# ai_orb-16.net
KiCad netlist of a schematic drawn in EAGLE
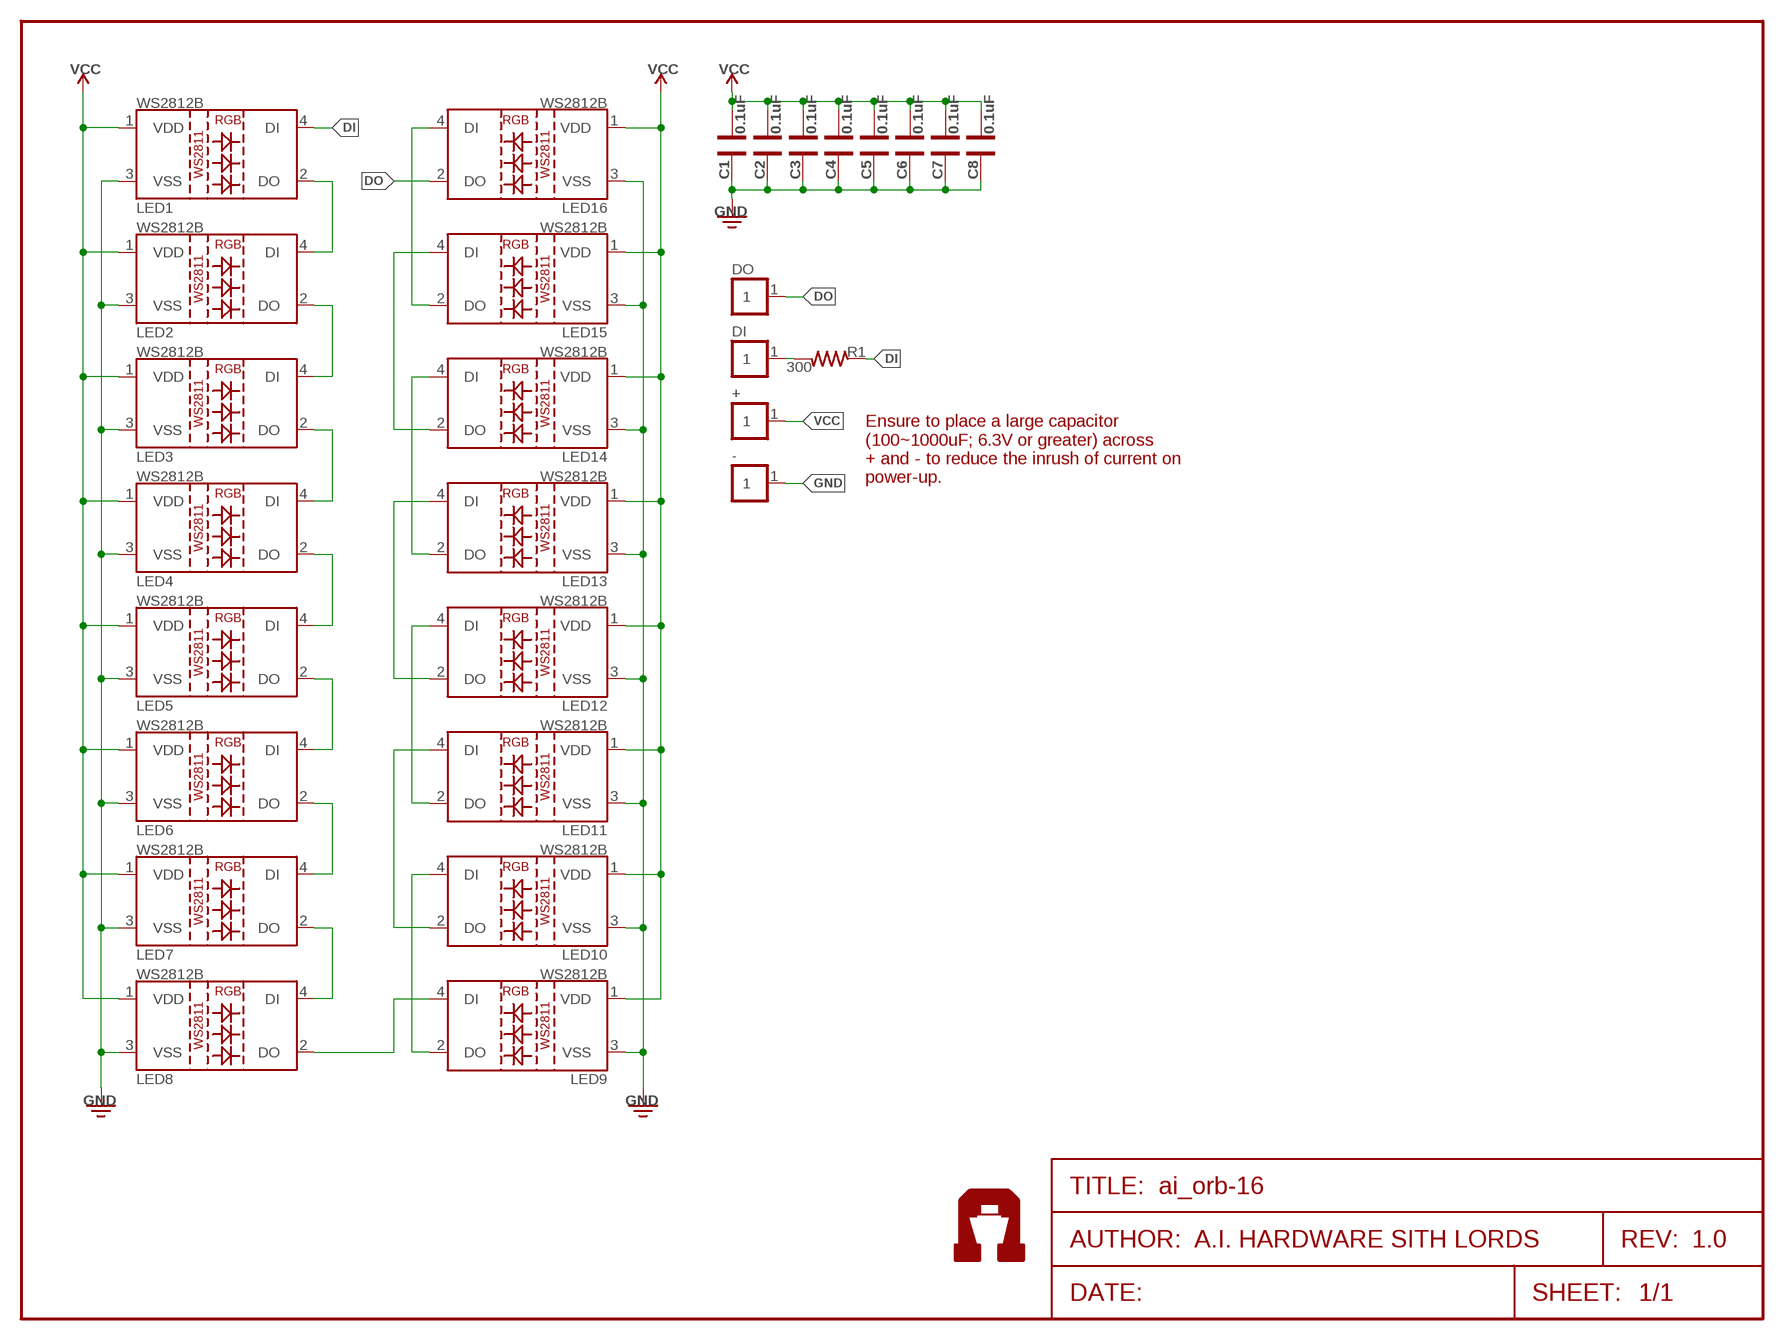
[diagram p0: schematic, sheet 1]

(export (version "E")
  (design (tool "Eeschema 10.0.6"))
  (components
    (comp (ref "+")
      (value "1X01-SM")
      (footprint "eagle-import:1X01-SM")
      (libsource (lib "eagle-import") (part "1X01-SM"))
    )
    (comp (ref "-")
      (value "1X01-SM")
      (footprint "eagle-import:1X01-SM")
      (libsource (lib "eagle-import") (part "1X01-SM"))
    )
    (comp (ref "C1")
      (value "0.1uF")
      (footprint "eagle-import:CAP-0402")
      (libsource (lib "eagle-import") (part "CAP0402"))
    )
    (comp (ref "C2")
      (value "0.1uF")
      (footprint "eagle-import:CAP-0402")
      (libsource (lib "eagle-import") (part "CAP0402"))
    )
    (comp (ref "C3")
      (value "0.1uF")
      (footprint "eagle-import:CAP-0402")
      (libsource (lib "eagle-import") (part "CAP0402"))
    )
    (comp (ref "C4")
      (value "0.1uF")
      (footprint "eagle-import:CAP-0402")
      (libsource (lib "eagle-import") (part "CAP0402"))
    )
    (comp (ref "C5")
      (value "0.1uF")
      (footprint "eagle-import:CAP-0402")
      (libsource (lib "eagle-import") (part "CAP0402"))
    )
    (comp (ref "C6")
      (value "0.1uF")
      (footprint "eagle-import:CAP-0402")
      (libsource (lib "eagle-import") (part "CAP0402"))
    )
    (comp (ref "C7")
      (value "0.1uF")
      (footprint "eagle-import:CAP-0402")
      (libsource (lib "eagle-import") (part "CAP0402"))
    )
    (comp (ref "C8")
      (value "0.1uF")
      (footprint "eagle-import:CAP-0402")
      (libsource (lib "eagle-import") (part "CAP0402"))
    )
    (comp (ref "DI")
      (value "1X01-SM")
      (footprint "eagle-import:1X01-SM")
      (libsource (lib "eagle-import") (part "1X01-SM"))
    )
    (comp (ref "DO")
      (value "1X01-SM")
      (footprint "eagle-import:1X01-SM")
      (libsource (lib "eagle-import") (part "1X01-SM"))
    )
    (comp (ref "LED1")
      (value "LED-WS2812B-SM")
      (footprint "eagle-import:LED-WS2812B-SM")
      (libsource (lib "eagle-import") (part "LED-WS2812B-SM"))
    )
    (comp (ref "LED2")
      (value "LED-WS2812B-SM")
      (footprint "eagle-import:LED-WS2812B-SM")
      (libsource (lib "eagle-import") (part "LED-WS2812B-SM"))
    )
    (comp (ref "LED3")
      (value "LED-WS2812B-SM")
      (footprint "eagle-import:LED-WS2812B-SM")
      (libsource (lib "eagle-import") (part "LED-WS2812B-SM"))
    )
    (comp (ref "LED4")
      (value "LED-WS2812B-SM")
      (footprint "eagle-import:LED-WS2812B-SM")
      (libsource (lib "eagle-import") (part "LED-WS2812B-SM"))
    )
    (comp (ref "LED5")
      (value "LED-WS2812B-SM")
      (footprint "eagle-import:LED-WS2812B-SM")
      (libsource (lib "eagle-import") (part "LED-WS2812B-SM"))
    )
    (comp (ref "LED6")
      (value "LED-WS2812B-SM")
      (footprint "eagle-import:LED-WS2812B-SM")
      (libsource (lib "eagle-import") (part "LED-WS2812B-SM"))
    )
    (comp (ref "LED7")
      (value "LED-WS2812B-SM")
      (footprint "eagle-import:LED-WS2812B-SM")
      (libsource (lib "eagle-import") (part "LED-WS2812B-SM"))
    )
    (comp (ref "LED8")
      (value "LED-WS2812B-SM")
      (footprint "eagle-import:LED-WS2812B-SM")
      (libsource (lib "eagle-import") (part "LED-WS2812B-SM"))
    )
    (comp (ref "LED9")
      (value "LED-WS2812B-SM")
      (footprint "eagle-import:LED-WS2812B-SM")
      (libsource (lib "eagle-import") (part "LED-WS2812B-SM"))
    )
    (comp (ref "LED10")
      (value "LED-WS2812B-SM")
      (footprint "eagle-import:LED-WS2812B-SM")
      (libsource (lib "eagle-import") (part "LED-WS2812B-SM"))
    )
    (comp (ref "LED11")
      (value "LED-WS2812B-SM")
      (footprint "eagle-import:LED-WS2812B-SM")
      (libsource (lib "eagle-import") (part "LED-WS2812B-SM"))
    )
    (comp (ref "LED12")
      (value "LED-WS2812B-SM")
      (footprint "eagle-import:LED-WS2812B-SM")
      (libsource (lib "eagle-import") (part "LED-WS2812B-SM"))
    )
    (comp (ref "LED13")
      (value "LED-WS2812B-SM")
      (footprint "eagle-import:LED-WS2812B-SM")
      (libsource (lib "eagle-import") (part "LED-WS2812B-SM"))
    )
    (comp (ref "LED14")
      (value "LED-WS2812B-SM")
      (footprint "eagle-import:LED-WS2812B-SM")
      (libsource (lib "eagle-import") (part "LED-WS2812B-SM"))
    )
    (comp (ref "LED15")
      (value "LED-WS2812B-SM")
      (footprint "eagle-import:LED-WS2812B-SM")
      (libsource (lib "eagle-import") (part "LED-WS2812B-SM"))
    )
    (comp (ref "LED16")
      (value "LED-WS2812B-SM")
      (footprint "eagle-import:LED-WS2812B-SM")
      (libsource (lib "eagle-import") (part "LED-WS2812B-SM"))
    )
    (comp (ref "LOGO")
      (value "AI-LOGOXS")
      (footprint "eagle-import:AI-LOGO-XS")
      (libsource (lib "eagle-import") (part "AI-LOGOXS"))
    )
    (comp (ref "R1")
      (value "300")
      (footprint "eagle-import:RES-0402")
      (libsource (lib "eagle-import") (part "RES0402"))
    )
  )
  (nets
    (net (code "1") (name "DI") (class "Default")
      (node (ref "LED1") (pin "4") (pinfunction "DI_4") (pintype "bidirectional"))
      (node (ref "R1") (pin "1") (pinfunction "1_1") (pintype "passive"))
    )
    (net (code "2") (name "DO") (class "Default")
      (node (ref "DO") (pin "1") (pinfunction "1_1") (pintype "bidirectional"))
      (node (ref "LED16") (pin "2") (pinfunction "DO_2") (pintype "bidirectional"))
    )
    (net (code "3") (name "GND") (class "Default")
      (node (ref "-") (pin "1") (pinfunction "1_1") (pintype "bidirectional"))
      (node (ref "C1") (pin "2") (pinfunction "2_2") (pintype "passive"))
      (node (ref "C2") (pin "2") (pinfunction "2_2") (pintype "passive"))
      (node (ref "C3") (pin "2") (pinfunction "2_2") (pintype "passive"))
      (node (ref "C4") (pin "2") (pinfunction "2_2") (pintype "passive"))
      (node (ref "C5") (pin "2") (pinfunction "2_2") (pintype "passive"))
      (node (ref "C6") (pin "2") (pinfunction "2_2") (pintype "passive"))
      (node (ref "C7") (pin "2") (pinfunction "2_2") (pintype "passive"))
      (node (ref "C8") (pin "2") (pinfunction "2_2") (pintype "passive"))
      (node (ref "LED1") (pin "3") (pinfunction "VSS_3") (pintype "bidirectional"))
      (node (ref "LED10") (pin "3") (pinfunction "VSS_3") (pintype "bidirectional"))
      (node (ref "LED11") (pin "3") (pinfunction "VSS_3") (pintype "bidirectional"))
      (node (ref "LED12") (pin "3") (pinfunction "VSS_3") (pintype "bidirectional"))
      (node (ref "LED13") (pin "3") (pinfunction "VSS_3") (pintype "bidirectional"))
      (node (ref "LED14") (pin "3") (pinfunction "VSS_3") (pintype "bidirectional"))
      (node (ref "LED15") (pin "3") (pinfunction "VSS_3") (pintype "bidirectional"))
      (node (ref "LED16") (pin "3") (pinfunction "VSS_3") (pintype "bidirectional"))
      (node (ref "LED2") (pin "3") (pinfunction "VSS_3") (pintype "bidirectional"))
      (node (ref "LED3") (pin "3") (pinfunction "VSS_3") (pintype "bidirectional"))
      (node (ref "LED4") (pin "3") (pinfunction "VSS_3") (pintype "bidirectional"))
      (node (ref "LED5") (pin "3") (pinfunction "VSS_3") (pintype "bidirectional"))
      (node (ref "LED6") (pin "3") (pinfunction "VSS_3") (pintype "bidirectional"))
      (node (ref "LED7") (pin "3") (pinfunction "VSS_3") (pintype "bidirectional"))
      (node (ref "LED8") (pin "3") (pinfunction "VSS_3") (pintype "bidirectional"))
      (node (ref "LED9") (pin "3") (pinfunction "VSS_3") (pintype "bidirectional"))
    )
    (net (code "4") (name "Net-(DI-Pad1)") (class "Default")
      (node (ref "DI") (pin "1") (pinfunction "1_1") (pintype "bidirectional"))
      (node (ref "R1") (pin "2") (pinfunction "2_2") (pintype "passive"))
    )
    (net (code "5") (name "Net-(LED1-DO)") (class "Default")
      (node (ref "LED1") (pin "2") (pinfunction "DO_2") (pintype "bidirectional"))
      (node (ref "LED2") (pin "4") (pinfunction "DI_4") (pintype "bidirectional"))
    )
    (net (code "6") (name "Net-(LED2-DO)") (class "Default")
      (node (ref "LED2") (pin "2") (pinfunction "DO_2") (pintype "bidirectional"))
      (node (ref "LED3") (pin "4") (pinfunction "DI_4") (pintype "bidirectional"))
    )
    (net (code "7") (name "Net-(LED3-DO)") (class "Default")
      (node (ref "LED3") (pin "2") (pinfunction "DO_2") (pintype "bidirectional"))
      (node (ref "LED4") (pin "4") (pinfunction "DI_4") (pintype "bidirectional"))
    )
    (net (code "8") (name "Net-(LED4-DO)") (class "Default")
      (node (ref "LED4") (pin "2") (pinfunction "DO_2") (pintype "bidirectional"))
      (node (ref "LED5") (pin "4") (pinfunction "DI_4") (pintype "bidirectional"))
    )
    (net (code "9") (name "Net-(LED5-DO)") (class "Default")
      (node (ref "LED5") (pin "2") (pinfunction "DO_2") (pintype "bidirectional"))
      (node (ref "LED6") (pin "4") (pinfunction "DI_4") (pintype "bidirectional"))
    )
    (net (code "10") (name "Net-(LED6-DO)") (class "Default")
      (node (ref "LED6") (pin "2") (pinfunction "DO_2") (pintype "bidirectional"))
      (node (ref "LED7") (pin "4") (pinfunction "DI_4") (pintype "bidirectional"))
    )
    (net (code "11") (name "Net-(LED7-DO)") (class "Default")
      (node (ref "LED7") (pin "2") (pinfunction "DO_2") (pintype "bidirectional"))
      (node (ref "LED8") (pin "4") (pinfunction "DI_4") (pintype "bidirectional"))
    )
    (net (code "12") (name "Net-(LED8-DO)") (class "Default")
      (node (ref "LED8") (pin "2") (pinfunction "DO_2") (pintype "bidirectional"))
      (node (ref "LED9") (pin "4") (pinfunction "DI_4") (pintype "bidirectional"))
    )
    (net (code "13") (name "Net-(LED10-DI)") (class "Default")
      (node (ref "LED10") (pin "4") (pinfunction "DI_4") (pintype "bidirectional"))
      (node (ref "LED9") (pin "2") (pinfunction "DO_2") (pintype "bidirectional"))
    )
    (net (code "14") (name "Net-(LED10-DO)") (class "Default")
      (node (ref "LED10") (pin "2") (pinfunction "DO_2") (pintype "bidirectional"))
      (node (ref "LED11") (pin "4") (pinfunction "DI_4") (pintype "bidirectional"))
    )
    (net (code "15") (name "Net-(LED11-DO)") (class "Default")
      (node (ref "LED11") (pin "2") (pinfunction "DO_2") (pintype "bidirectional"))
      (node (ref "LED12") (pin "4") (pinfunction "DI_4") (pintype "bidirectional"))
    )
    (net (code "16") (name "Net-(LED12-DO)") (class "Default")
      (node (ref "LED12") (pin "2") (pinfunction "DO_2") (pintype "bidirectional"))
      (node (ref "LED13") (pin "4") (pinfunction "DI_4") (pintype "bidirectional"))
    )
    (net (code "17") (name "Net-(LED13-DO)") (class "Default")
      (node (ref "LED13") (pin "2") (pinfunction "DO_2") (pintype "bidirectional"))
      (node (ref "LED14") (pin "4") (pinfunction "DI_4") (pintype "bidirectional"))
    )
    (net (code "18") (name "Net-(LED14-DO)") (class "Default")
      (node (ref "LED14") (pin "2") (pinfunction "DO_2") (pintype "bidirectional"))
      (node (ref "LED15") (pin "4") (pinfunction "DI_4") (pintype "bidirectional"))
    )
    (net (code "19") (name "Net-(LED15-DO)") (class "Default")
      (node (ref "LED15") (pin "2") (pinfunction "DO_2") (pintype "bidirectional"))
      (node (ref "LED16") (pin "4") (pinfunction "DI_4") (pintype "bidirectional"))
    )
    (net (code "20") (name "VCC") (class "Default")
      (node (ref "+") (pin "1") (pinfunction "1_1") (pintype "bidirectional"))
      (node (ref "C1") (pin "1") (pinfunction "1_1") (pintype "passive"))
      (node (ref "C2") (pin "1") (pinfunction "1_1") (pintype "passive"))
      (node (ref "C3") (pin "1") (pinfunction "1_1") (pintype "passive"))
      (node (ref "C4") (pin "1") (pinfunction "1_1") (pintype "passive"))
      (node (ref "C5") (pin "1") (pinfunction "1_1") (pintype "passive"))
      (node (ref "C6") (pin "1") (pinfunction "1_1") (pintype "passive"))
      (node (ref "C7") (pin "1") (pinfunction "1_1") (pintype "passive"))
      (node (ref "C8") (pin "1") (pinfunction "1_1") (pintype "passive"))
      (node (ref "LED1") (pin "1") (pinfunction "VDD_1") (pintype "bidirectional"))
      (node (ref "LED10") (pin "1") (pinfunction "VDD_1") (pintype "bidirectional"))
      (node (ref "LED11") (pin "1") (pinfunction "VDD_1") (pintype "bidirectional"))
      (node (ref "LED12") (pin "1") (pinfunction "VDD_1") (pintype "bidirectional"))
      (node (ref "LED13") (pin "1") (pinfunction "VDD_1") (pintype "bidirectional"))
      (node (ref "LED14") (pin "1") (pinfunction "VDD_1") (pintype "bidirectional"))
      (node (ref "LED15") (pin "1") (pinfunction "VDD_1") (pintype "bidirectional"))
      (node (ref "LED16") (pin "1") (pinfunction "VDD_1") (pintype "bidirectional"))
      (node (ref "LED2") (pin "1") (pinfunction "VDD_1") (pintype "bidirectional"))
      (node (ref "LED3") (pin "1") (pinfunction "VDD_1") (pintype "bidirectional"))
      (node (ref "LED4") (pin "1") (pinfunction "VDD_1") (pintype "bidirectional"))
      (node (ref "LED5") (pin "1") (pinfunction "VDD_1") (pintype "bidirectional"))
      (node (ref "LED6") (pin "1") (pinfunction "VDD_1") (pintype "bidirectional"))
      (node (ref "LED7") (pin "1") (pinfunction "VDD_1") (pintype "bidirectional"))
      (node (ref "LED8") (pin "1") (pinfunction "VDD_1") (pintype "bidirectional"))
      (node (ref "LED9") (pin "1") (pinfunction "VDD_1") (pintype "bidirectional"))
    )
  )
)
